# untitled.net
KiCad netlist of a schematic drawn in EAGLE
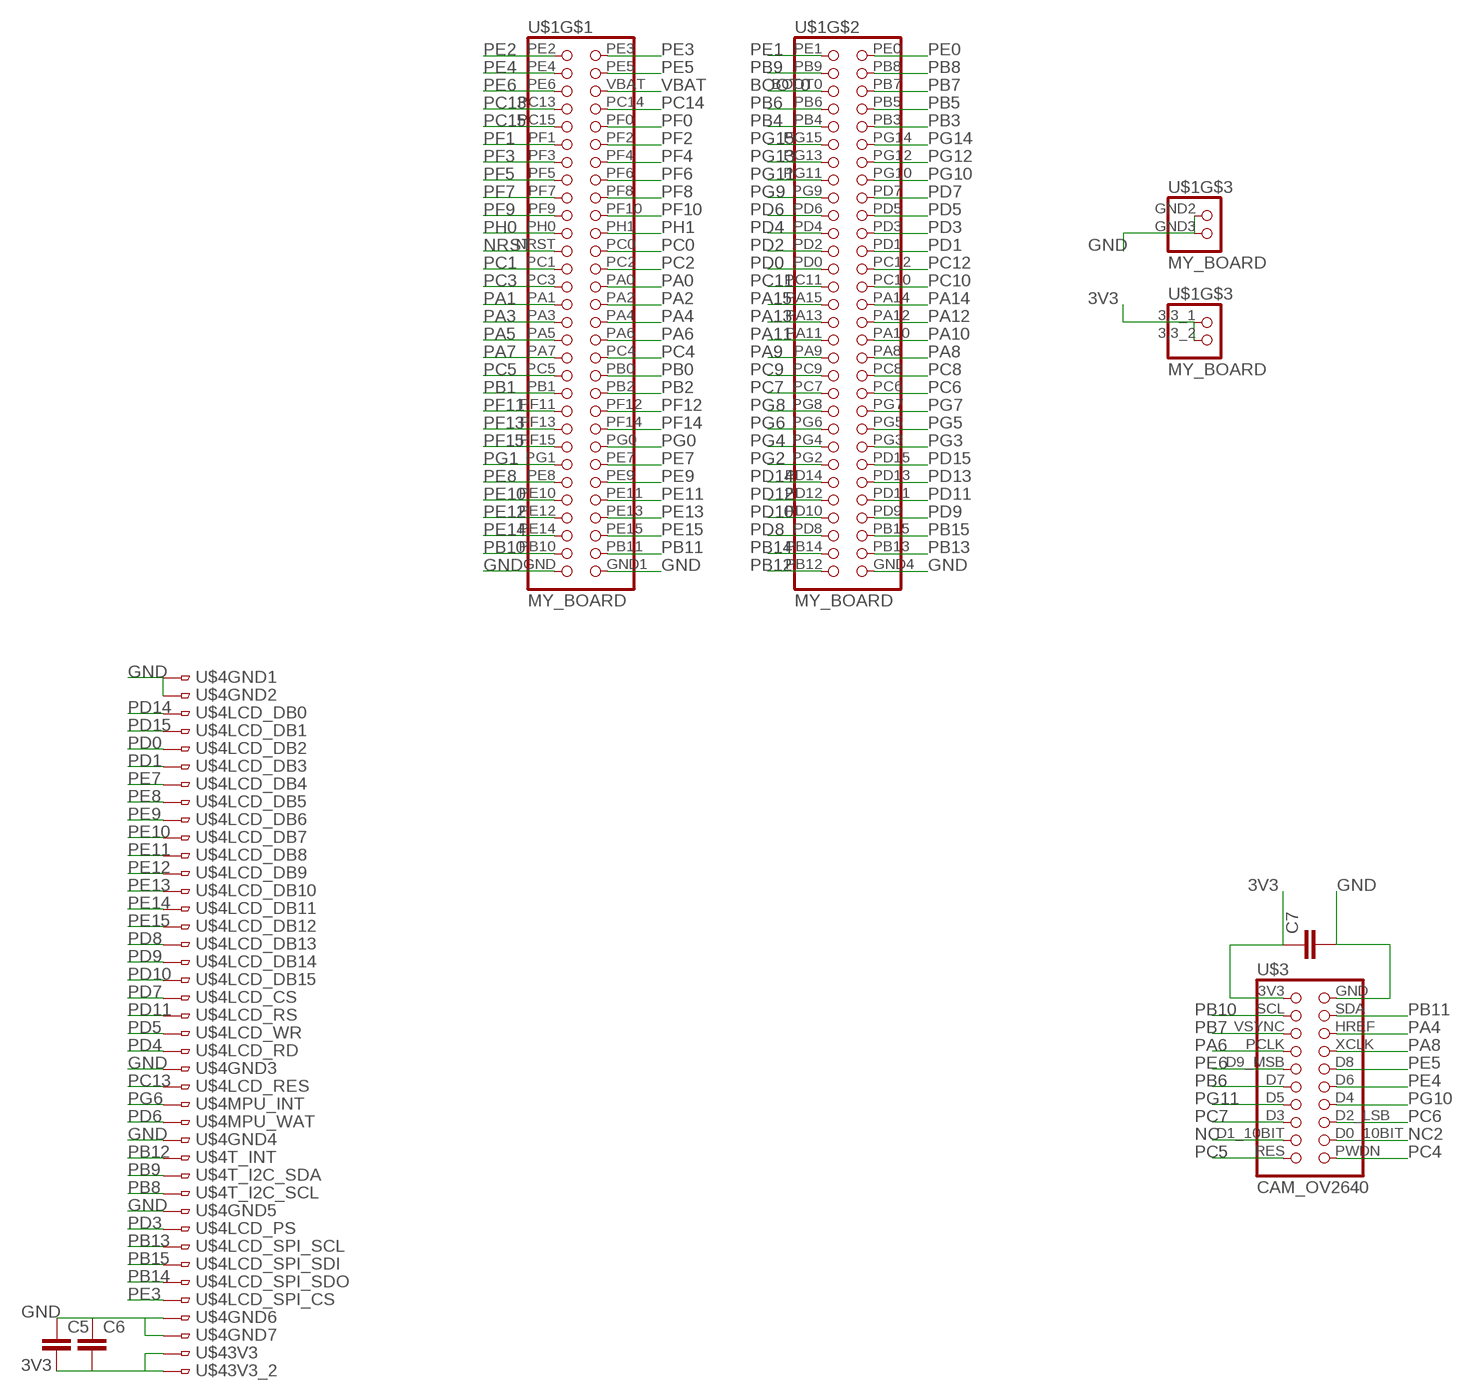
[diagram p0: schematic, sheet 1]

(export (version "E")
  (design (tool "Eeschema 10.0.6"))
  (components
    (comp (ref "C5")
      (value "C-EUC1206")
      (footprint "eagle-import:C1206")
      (libsource (lib "eagle-import") (part "C-EUC1206"))
    )
    (comp (ref "C6")
      (value "C-EUC1206")
      (footprint "eagle-import:C1206")
      (libsource (lib "eagle-import") (part "C-EUC1206"))
    )
    (comp (ref "C7")
      (value "C-EUC1206")
      (footprint "eagle-import:C1206")
      (libsource (lib "eagle-import") (part "C-EUC1206"))
    )
    (comp (ref "U$1")
      (value "MY_BOARD")
      (footprint "eagle-import:MY_BOARD")
      (libsource (lib "eagle-import") (part "MY_BOARD"))
    )
    (comp (ref "U$3")
      (value "CAM_OV2640")
      (footprint "eagle-import:CAM_OV2640")
      (libsource (lib "eagle-import") (part "CAM_OV2640"))
    )
    (comp (ref "U$4")
      (value "LCD800TFT")
      (footprint "eagle-import:FH12-40S-0.5SH")
      (libsource (lib "eagle-import") (part "LCD800TFT"))
    )
  )
  (nets
    (net (code "1") (name "/3V3") (class "Default")
      (node (ref "C5") (pin "2") (pinfunction "2_2") (pintype "passive"))
      (node (ref "C6") (pin "2") (pinfunction "2_2") (pintype "passive"))
      (node (ref "C7") (pin "1") (pinfunction "1_1") (pintype "passive"))
      (node (ref "U$1") (pin "3,3_1") (pinfunction "1_3,3_1") (pintype "passive"))
      (node (ref "U$1") (pin "3,3_2") (pinfunction "2_3,3_2") (pintype "passive"))
      (node (ref "U$3") (pin "3V3") (pinfunction "3V3_3V3") (pintype "passive"))
      (node (ref "U$4") (pin "39") (pinfunction "1_39") (pintype "passive"))
      (node (ref "U$4") (pin "40") (pinfunction "1_40") (pintype "passive"))
    )
    (net (code "2") (name "/BOOT0") (class "Default")
      (node (ref "U$1") (pin "BOOT0") (pinfunction "5_BOOT0") (pintype "passive"))
    )
    (net (code "3") (name "/GND") (class "Default")
      (node (ref "C5") (pin "1") (pinfunction "1_1") (pintype "passive"))
      (node (ref "C6") (pin "1") (pinfunction "1_1") (pintype "passive"))
      (node (ref "C7") (pin "2") (pinfunction "2_2") (pintype "passive"))
      (node (ref "U$1") (pin "GND") (pinfunction "59_GND") (pintype "passive"))
      (node (ref "U$1") (pin "GND1") (pinfunction "60_GND1") (pintype "passive"))
      (node (ref "U$1") (pin "GND2") (pinfunction "3_GND2") (pintype "passive"))
      (node (ref "U$1") (pin "GND3") (pinfunction "4_GND3") (pintype "passive"))
      (node (ref "U$1") (pin "GND4") (pinfunction "60_GND4") (pintype "passive"))
      (node (ref "U$3") (pin "GND") (pinfunction "GND_GND") (pintype "passive"))
      (node (ref "U$4") (pin "1") (pinfunction "1_1") (pintype "passive"))
      (node (ref "U$4") (pin "2") (pinfunction "1_2") (pintype "passive"))
      (node (ref "U$4") (pin "23") (pinfunction "1_23") (pintype "passive"))
      (node (ref "U$4") (pin "27") (pinfunction "1_27") (pintype "passive"))
      (node (ref "U$4") (pin "31") (pinfunction "1_31") (pintype "passive"))
      (node (ref "U$4") (pin "37") (pinfunction "1_37") (pintype "passive"))
      (node (ref "U$4") (pin "38") (pinfunction "1_38") (pintype "passive"))
    )
    (net (code "4") (name "/NC") (class "Default")
      (node (ref "U$3") (pin "D1_10BIT") (pinfunction "D1_10BIT_D1_10BIT") (pintype "passive"))
    )
    (net (code "5") (name "/NC2") (class "Default")
      (node (ref "U$3") (pin "D0_10BIT") (pinfunction "D0_10BIT_D0_10BIT") (pintype "passive"))
    )
    (net (code "6") (name "/NRST") (class "Default")
      (node (ref "U$1") (pin "NRST") (pinfunction "23_NRST") (pintype "passive"))
    )
    (net (code "7") (name "/PA0") (class "Default")
      (node (ref "U$1") (pin "PA0") (pinfunction "28_PA0") (pintype "passive"))
    )
    (net (code "8") (name "/PA1") (class "Default")
      (node (ref "U$1") (pin "PA1") (pinfunction "29_PA1") (pintype "passive"))
    )
    (net (code "9") (name "/PA2") (class "Default")
      (node (ref "U$1") (pin "PA2") (pinfunction "30_PA2") (pintype "passive"))
    )
    (net (code "10") (name "/PA3") (class "Default")
      (node (ref "U$1") (pin "PA3") (pinfunction "31_PA3") (pintype "passive"))
    )
    (net (code "11") (name "/PA4") (class "Default")
      (node (ref "U$1") (pin "PA4") (pinfunction "32_PA4") (pintype "passive"))
      (node (ref "U$3") (pin "HREF") (pinfunction "HREF_HREF") (pintype "passive"))
    )
    (net (code "12") (name "/PA5") (class "Default")
      (node (ref "U$1") (pin "PA5") (pinfunction "33_PA5") (pintype "passive"))
    )
    (net (code "13") (name "/PA6") (class "Default")
      (node (ref "U$1") (pin "PA6") (pinfunction "34_PA6") (pintype "passive"))
      (node (ref "U$3") (pin "PCLK") (pinfunction "PCLK_PCLK") (pintype "passive"))
    )
    (net (code "14") (name "/PA7") (class "Default")
      (node (ref "U$1") (pin "PA7") (pinfunction "35_PA7") (pintype "passive"))
    )
    (net (code "15") (name "/PA8") (class "Default")
      (node (ref "U$1") (pin "PA8") (pinfunction "36_PA8") (pintype "passive"))
      (node (ref "U$3") (pin "XCLK") (pinfunction "XCLK_XCLK") (pintype "passive"))
    )
    (net (code "16") (name "/PA9") (class "Default")
      (node (ref "U$1") (pin "PA9") (pinfunction "35_PA9") (pintype "passive"))
    )
    (net (code "17") (name "/PA10") (class "Default")
      (node (ref "U$1") (pin "PA10") (pinfunction "34_PA10") (pintype "passive"))
    )
    (net (code "18") (name "/PA11") (class "Default")
      (node (ref "U$1") (pin "PA11") (pinfunction "33_PA11") (pintype "passive"))
    )
    (net (code "19") (name "/PA12") (class "Default")
      (node (ref "U$1") (pin "PA12") (pinfunction "32_PA12") (pintype "passive"))
    )
    (net (code "20") (name "/PA13") (class "Default")
      (node (ref "U$1") (pin "PA13") (pinfunction "31_PA13") (pintype "passive"))
    )
    (net (code "21") (name "/PA14") (class "Default")
      (node (ref "U$1") (pin "PA14") (pinfunction "30_PA14") (pintype "passive"))
    )
    (net (code "22") (name "/PA15") (class "Default")
      (node (ref "U$1") (pin "PA15") (pinfunction "29_PA15") (pintype "passive"))
    )
    (net (code "23") (name "/PB0") (class "Default")
      (node (ref "U$1") (pin "PB0") (pinfunction "38_PB0") (pintype "passive"))
    )
    (net (code "24") (name "/PB1") (class "Default")
      (node (ref "U$1") (pin "PB1") (pinfunction "39_PB1") (pintype "passive"))
    )
    (net (code "25") (name "/PB2") (class "Default")
      (node (ref "U$1") (pin "PB2") (pinfunction "40_PB2") (pintype "passive"))
    )
    (net (code "26") (name "/PB3") (class "Default")
      (node (ref "U$1") (pin "PB3") (pinfunction "10_PB3") (pintype "passive"))
    )
    (net (code "27") (name "/PB4") (class "Default")
      (node (ref "U$1") (pin "PB4") (pinfunction "9_PB4") (pintype "passive"))
    )
    (net (code "28") (name "/PB5") (class "Default")
      (node (ref "U$1") (pin "PB5") (pinfunction "8_PB5") (pintype "passive"))
    )
    (net (code "29") (name "/PB6") (class "Default")
      (node (ref "U$1") (pin "PB6") (pinfunction "7_PB6") (pintype "passive"))
      (node (ref "U$3") (pin "D7") (pinfunction "D7_D7") (pintype "passive"))
    )
    (net (code "30") (name "/PB7") (class "Default")
      (node (ref "U$1") (pin "PB7") (pinfunction "6_PB7") (pintype "passive"))
      (node (ref "U$3") (pin "VSYNC") (pinfunction "VSYNC_VSYNC") (pintype "passive"))
    )
    (net (code "31") (name "/PB8") (class "Default")
      (node (ref "U$1") (pin "PB8") (pinfunction "4_PB8") (pintype "passive"))
      (node (ref "U$4") (pin "30") (pinfunction "1_30") (pintype "passive"))
    )
    (net (code "32") (name "/PB9") (class "Default")
      (node (ref "U$1") (pin "PB9") (pinfunction "3_PB9") (pintype "passive"))
      (node (ref "U$4") (pin "29") (pinfunction "1_29") (pintype "passive"))
    )
    (net (code "33") (name "/PB10") (class "Default")
      (node (ref "U$1") (pin "PB10") (pinfunction "57_PB10") (pintype "passive"))
      (node (ref "U$3") (pin "SCL") (pinfunction "SCL_SCL") (pintype "passive"))
    )
    (net (code "34") (name "/PB11") (class "Default")
      (node (ref "U$1") (pin "PB11") (pinfunction "58_PB11") (pintype "passive"))
      (node (ref "U$3") (pin "SDA") (pinfunction "SDA_SDA") (pintype "passive"))
    )
    (net (code "35") (name "/PB12") (class "Default")
      (node (ref "U$1") (pin "PB12") (pinfunction "59_PB12") (pintype "passive"))
      (node (ref "U$4") (pin "28") (pinfunction "1_28") (pintype "passive"))
    )
    (net (code "36") (name "/PB13") (class "Default")
      (node (ref "U$1") (pin "PB13") (pinfunction "58_PB13") (pintype "passive"))
      (node (ref "U$4") (pin "33") (pinfunction "1_33") (pintype "passive"))
    )
    (net (code "37") (name "/PB14") (class "Default")
      (node (ref "U$1") (pin "PB14") (pinfunction "57_PB14") (pintype "passive"))
      (node (ref "U$4") (pin "35") (pinfunction "1_35") (pintype "passive"))
    )
    (net (code "38") (name "/PB15") (class "Default")
      (node (ref "U$1") (pin "PB15") (pinfunction "56_PB15") (pintype "passive"))
      (node (ref "U$4") (pin "34") (pinfunction "1_34") (pintype "passive"))
    )
    (net (code "39") (name "/PC0") (class "Default")
      (node (ref "U$1") (pin "PC0") (pinfunction "24_PC0") (pintype "passive"))
    )
    (net (code "40") (name "/PC1") (class "Default")
      (node (ref "U$1") (pin "PC1") (pinfunction "25_PC1") (pintype "passive"))
    )
    (net (code "41") (name "/PC2") (class "Default")
      (node (ref "U$1") (pin "PC2") (pinfunction "26_PC2") (pintype "passive"))
    )
    (net (code "42") (name "/PC3") (class "Default")
      (node (ref "U$1") (pin "PC3") (pinfunction "27_PC3") (pintype "passive"))
    )
    (net (code "43") (name "/PC4") (class "Default")
      (node (ref "U$1") (pin "PC4") (pinfunction "36_PC4") (pintype "passive"))
      (node (ref "U$3") (pin "PWDN") (pinfunction "PWDN_PWDN") (pintype "passive"))
    )
    (net (code "44") (name "/PC5") (class "Default")
      (node (ref "U$1") (pin "PC5") (pinfunction "37_PC5") (pintype "passive"))
      (node (ref "U$3") (pin "RES") (pinfunction "RES_RES") (pintype "passive"))
    )
    (net (code "45") (name "/PC6") (class "Default")
      (node (ref "U$1") (pin "PC6") (pinfunction "40_PC6") (pintype "passive"))
      (node (ref "U$3") (pin "D2_LSB") (pinfunction "D2_LSB_D2_LSB") (pintype "passive"))
    )
    (net (code "46") (name "/PC7") (class "Default")
      (node (ref "U$1") (pin "PC7") (pinfunction "39_PC7") (pintype "passive"))
      (node (ref "U$3") (pin "D3") (pinfunction "D3_D3") (pintype "passive"))
    )
    (net (code "47") (name "/PC8") (class "Default")
      (node (ref "U$1") (pin "PC8") (pinfunction "38_PC8") (pintype "passive"))
    )
    (net (code "48") (name "/PC9") (class "Default")
      (node (ref "U$1") (pin "PC9") (pinfunction "37_PC9") (pintype "passive"))
    )
    (net (code "49") (name "/PC10") (class "Default")
      (node (ref "U$1") (pin "PC10") (pinfunction "28_PC10") (pintype "passive"))
    )
    (net (code "50") (name "/PC11") (class "Default")
      (node (ref "U$1") (pin "PC11") (pinfunction "27_PC11") (pintype "passive"))
    )
    (net (code "51") (name "/PC12") (class "Default")
      (node (ref "U$1") (pin "PC12") (pinfunction "26_PC12") (pintype "passive"))
    )
    (net (code "52") (name "/PC13") (class "Default")
      (node (ref "U$1") (pin "PC13") (pinfunction "7_PC13") (pintype "passive"))
      (node (ref "U$4") (pin "24") (pinfunction "1_24") (pintype "passive"))
    )
    (net (code "53") (name "/PC14") (class "Default")
      (node (ref "U$1") (pin "PC14") (pinfunction "8_PC14") (pintype "passive"))
    )
    (net (code "54") (name "/PC15") (class "Default")
      (node (ref "U$1") (pin "PC15") (pinfunction "9_PC15") (pintype "passive"))
    )
    (net (code "55") (name "/PD0") (class "Default")
      (node (ref "U$1") (pin "PD0") (pinfunction "25_PD0") (pintype "passive"))
      (node (ref "U$4") (pin "5") (pinfunction "1_5") (pintype "passive"))
    )
    (net (code "56") (name "/PD1") (class "Default")
      (node (ref "U$1") (pin "PD1") (pinfunction "24_PD1") (pintype "passive"))
      (node (ref "U$4") (pin "6") (pinfunction "1_6") (pintype "passive"))
    )
    (net (code "57") (name "/PD2") (class "Default")
      (node (ref "U$1") (pin "PD2") (pinfunction "23_PD2") (pintype "passive"))
    )
    (net (code "58") (name "/PD3") (class "Default")
      (node (ref "U$1") (pin "PD3") (pinfunction "22_PD3") (pintype "passive"))
      (node (ref "U$4") (pin "32") (pinfunction "1_32") (pintype "passive"))
    )
    (net (code "59") (name "/PD4") (class "Default")
      (node (ref "U$1") (pin "PD4") (pinfunction "21_PD4") (pintype "passive"))
      (node (ref "U$4") (pin "22") (pinfunction "1_22") (pintype "passive"))
    )
    (net (code "60") (name "/PD5") (class "Default")
      (node (ref "U$1") (pin "PD5") (pinfunction "20_PD5") (pintype "passive"))
      (node (ref "U$4") (pin "21") (pinfunction "1_21") (pintype "passive"))
    )
    (net (code "61") (name "/PD6") (class "Default")
      (node (ref "U$1") (pin "PD6") (pinfunction "19_PD6") (pintype "passive"))
      (node (ref "U$4") (pin "26") (pinfunction "1_26") (pintype "passive"))
    )
    (net (code "62") (name "/PD7") (class "Default")
      (node (ref "U$1") (pin "PD7") (pinfunction "18_PD7") (pintype "passive"))
      (node (ref "U$4") (pin "19") (pinfunction "1_19") (pintype "passive"))
    )
    (net (code "63") (name "/PD8") (class "Default")
      (node (ref "U$1") (pin "PD8") (pinfunction "55_PD8") (pintype "passive"))
      (node (ref "U$4") (pin "16") (pinfunction "1_16") (pintype "passive"))
    )
    (net (code "64") (name "/PD9") (class "Default")
      (node (ref "U$1") (pin "PD9") (pinfunction "54_PD9") (pintype "passive"))
      (node (ref "U$4") (pin "17") (pinfunction "1_17") (pintype "passive"))
    )
    (net (code "65") (name "/PD10") (class "Default")
      (node (ref "U$1") (pin "PD10") (pinfunction "53_PD10") (pintype "passive"))
      (node (ref "U$4") (pin "18") (pinfunction "1_18") (pintype "passive"))
    )
    (net (code "66") (name "/PD11") (class "Default")
      (node (ref "U$1") (pin "PD11") (pinfunction "52_PD11") (pintype "passive"))
      (node (ref "U$4") (pin "20") (pinfunction "1_20") (pintype "passive"))
    )
    (net (code "67") (name "/PD12") (class "Default")
      (node (ref "U$1") (pin "PD12") (pinfunction "51_PD12") (pintype "passive"))
    )
    (net (code "68") (name "/PD13") (class "Default")
      (node (ref "U$1") (pin "PD13") (pinfunction "50_PD13") (pintype "passive"))
    )
    (net (code "69") (name "/PD14") (class "Default")
      (node (ref "U$1") (pin "PD14") (pinfunction "49_PD14") (pintype "passive"))
      (node (ref "U$4") (pin "3") (pinfunction "1_3") (pintype "passive"))
    )
    (net (code "70") (name "/PD15") (class "Default")
      (node (ref "U$1") (pin "PD15") (pinfunction "48_PD15") (pintype "passive"))
      (node (ref "U$4") (pin "4") (pinfunction "1_4") (pintype "passive"))
    )
    (net (code "71") (name "/PE0") (class "Default")
      (node (ref "U$1") (pin "PE0") (pinfunction "2_PE0") (pintype "passive"))
    )
    (net (code "72") (name "/PE1") (class "Default")
      (node (ref "U$1") (pin "PE1") (pinfunction "1_PE1") (pintype "passive"))
    )
    (net (code "73") (name "/PE2") (class "Default")
      (node (ref "U$1") (pin "PE2") (pinfunction "1_PE2") (pintype "passive"))
    )
    (net (code "74") (name "/PE3") (class "Default")
      (node (ref "U$1") (pin "PE3") (pinfunction "2_PE3") (pintype "passive"))
      (node (ref "U$4") (pin "36") (pinfunction "1_36") (pintype "passive"))
    )
    (net (code "75") (name "/PE4") (class "Default")
      (node (ref "U$1") (pin "PE4") (pinfunction "3_PE4") (pintype "passive"))
      (node (ref "U$3") (pin "D6") (pinfunction "D6_D6") (pintype "passive"))
    )
    (net (code "76") (name "/PE5") (class "Default")
      (node (ref "U$1") (pin "PE5") (pinfunction "4_PE5") (pintype "passive"))
      (node (ref "U$3") (pin "D8") (pinfunction "D8_D8") (pintype "passive"))
    )
    (net (code "77") (name "/PE6") (class "Default")
      (node (ref "U$1") (pin "PE6") (pinfunction "5_PE6") (pintype "passive"))
      (node (ref "U$3") (pin "D9_MSB") (pinfunction "D9_MSB_D9_MSB") (pintype "passive"))
    )
    (net (code "78") (name "/PE7") (class "Default")
      (node (ref "U$1") (pin "PE7") (pinfunction "48_PE7") (pintype "passive"))
      (node (ref "U$4") (pin "7") (pinfunction "1_7") (pintype "passive"))
    )
    (net (code "79") (name "/PE8") (class "Default")
      (node (ref "U$1") (pin "PE8") (pinfunction "49_PE8") (pintype "passive"))
      (node (ref "U$4") (pin "8") (pinfunction "1_8") (pintype "passive"))
    )
    (net (code "80") (name "/PE9") (class "Default")
      (node (ref "U$1") (pin "PE9") (pinfunction "50_PE9") (pintype "passive"))
      (node (ref "U$4") (pin "9") (pinfunction "1_9") (pintype "passive"))
    )
    (net (code "81") (name "/PE10") (class "Default")
      (node (ref "U$1") (pin "PE10") (pinfunction "51_PE10") (pintype "passive"))
      (node (ref "U$4") (pin "10") (pinfunction "1_10") (pintype "passive"))
    )
    (net (code "82") (name "/PE11") (class "Default")
      (node (ref "U$1") (pin "PE11") (pinfunction "52_PE11") (pintype "passive"))
      (node (ref "U$4") (pin "11") (pinfunction "1_11") (pintype "passive"))
    )
    (net (code "83") (name "/PE12") (class "Default")
      (node (ref "U$1") (pin "PE12") (pinfunction "53_PE12") (pintype "passive"))
      (node (ref "U$4") (pin "12") (pinfunction "1_12") (pintype "passive"))
    )
    (net (code "84") (name "/PE13") (class "Default")
      (node (ref "U$1") (pin "PE13") (pinfunction "54_PE13") (pintype "passive"))
      (node (ref "U$4") (pin "13") (pinfunction "1_13") (pintype "passive"))
    )
    (net (code "85") (name "/PE14") (class "Default")
      (node (ref "U$1") (pin "PE14") (pinfunction "55_PE14") (pintype "passive"))
      (node (ref "U$4") (pin "14") (pinfunction "1_14") (pintype "passive"))
    )
    (net (code "86") (name "/PE15") (class "Default")
      (node (ref "U$1") (pin "PE15") (pinfunction "56_PE15") (pintype "passive"))
      (node (ref "U$4") (pin "15") (pinfunction "1_15") (pintype "passive"))
    )
    (net (code "87") (name "/PF0") (class "Default")
      (node (ref "U$1") (pin "PF0") (pinfunction "10_PF0") (pintype "passive"))
    )
    (net (code "88") (name "/PF1") (class "Default")
      (node (ref "U$1") (pin "PF1") (pinfunction "11_PF1") (pintype "passive"))
    )
    (net (code "89") (name "/PF2") (class "Default")
      (node (ref "U$1") (pin "PF2") (pinfunction "12_PF2") (pintype "passive"))
    )
    (net (code "90") (name "/PF3") (class "Default")
      (node (ref "U$1") (pin "PF3") (pinfunction "13_PF3") (pintype "passive"))
    )
    (net (code "91") (name "/PF4") (class "Default")
      (node (ref "U$1") (pin "PF4") (pinfunction "14_PF4") (pintype "passive"))
    )
    (net (code "92") (name "/PF5") (class "Default")
      (node (ref "U$1") (pin "PF5") (pinfunction "15_PF5") (pintype "passive"))
    )
    (net (code "93") (name "/PF6") (class "Default")
      (node (ref "U$1") (pin "PF6") (pinfunction "16_PF6") (pintype "passive"))
    )
    (net (code "94") (name "/PF7") (class "Default")
      (node (ref "U$1") (pin "PF7") (pinfunction "17_PF7") (pintype "passive"))
    )
    (net (code "95") (name "/PF8") (class "Default")
      (node (ref "U$1") (pin "PF8") (pinfunction "18_PF8") (pintype "passive"))
    )
    (net (code "96") (name "/PF9") (class "Default")
      (node (ref "U$1") (pin "PF9") (pinfunction "19_PF9") (pintype "passive"))
    )
    (net (code "97") (name "/PF10") (class "Default")
      (node (ref "U$1") (pin "PF10") (pinfunction "20_PF10") (pintype "passive"))
    )
    (net (code "98") (name "/PF11") (class "Default")
      (node (ref "U$1") (pin "PF11") (pinfunction "41_PF11") (pintype "passive"))
    )
    (net (code "99") (name "/PF12") (class "Default")
      (node (ref "U$1") (pin "PF12") (pinfunction "42_PF12") (pintype "passive"))
    )
    (net (code "100") (name "/PF13") (class "Default")
      (node (ref "U$1") (pin "PF13") (pinfunction "43_PF13") (pintype "passive"))
    )
    (net (code "101") (name "/PF14") (class "Default")
      (node (ref "U$1") (pin "PF14") (pinfunction "44_PF14") (pintype "passive"))
    )
    (net (code "102") (name "/PF15") (class "Default")
      (node (ref "U$1") (pin "PF15") (pinfunction "45_PF15") (pintype "passive"))
    )
    (net (code "103") (name "/PG0") (class "Default")
      (node (ref "U$1") (pin "PG0") (pinfunction "46_PG0") (pintype "passive"))
    )
    (net (code "104") (name "/PG1") (class "Default")
      (node (ref "U$1") (pin "PG1") (pinfunction "47_PG1") (pintype "passive"))
    )
    (net (code "105") (name "/PG2") (class "Default")
      (node (ref "U$1") (pin "PG2") (pinfunction "47_PG2") (pintype "passive"))
    )
    (net (code "106") (name "/PG3") (class "Default")
      (node (ref "U$1") (pin "PG3") (pinfunction "46_PG3") (pintype "passive"))
    )
    (net (code "107") (name "/PG4") (class "Default")
      (node (ref "U$1") (pin "PG4") (pinfunction "45_PG4") (pintype "passive"))
    )
    (net (code "108") (name "/PG5") (class "Default")
      (node (ref "U$1") (pin "PG5") (pinfunction "44_PG5") (pintype "passive"))
    )
    (net (code "109") (name "/PG6") (class "Default")
      (node (ref "U$1") (pin "PG6") (pinfunction "43_PG6") (pintype "passive"))
      (node (ref "U$4") (pin "25") (pinfunction "1_25") (pintype "passive"))
    )
    (net (code "110") (name "/PG7") (class "Default")
      (node (ref "U$1") (pin "PG7") (pinfunction "42_PG7") (pintype "passive"))
    )
    (net (code "111") (name "/PG8") (class "Default")
      (node (ref "U$1") (pin "PG8") (pinfunction "41_PG8") (pintype "passive"))
    )
    (net (code "112") (name "/PG9") (class "Default")
      (node (ref "U$1") (pin "PG9") (pinfunction "17_PG9") (pintype "passive"))
    )
    (net (code "113") (name "/PG10") (class "Default")
      (node (ref "U$1") (pin "PG10") (pinfunction "16_PG10") (pintype "passive"))
      (node (ref "U$3") (pin "D4") (pinfunction "D4_D4") (pintype "passive"))
    )
    (net (code "114") (name "/PG11") (class "Default")
      (node (ref "U$1") (pin "PG11") (pinfunction "15_PG11") (pintype "passive"))
      (node (ref "U$3") (pin "D5") (pinfunction "D5_D5") (pintype "passive"))
    )
    (net (code "115") (name "/PG12") (class "Default")
      (node (ref "U$1") (pin "PG12") (pinfunction "14_PG12") (pintype "passive"))
    )
    (net (code "116") (name "/PG13") (class "Default")
      (node (ref "U$1") (pin "PG13") (pinfunction "13_PG13") (pintype "passive"))
    )
    (net (code "117") (name "/PG14") (class "Default")
      (node (ref "U$1") (pin "PG14") (pinfunction "12_PG14") (pintype "passive"))
    )
    (net (code "118") (name "/PG15") (class "Default")
      (node (ref "U$1") (pin "PG15") (pinfunction "11_PG15") (pintype "passive"))
    )
    (net (code "119") (name "/PH0") (class "Default")
      (node (ref "U$1") (pin "PH0") (pinfunction "21_PH0") (pintype "passive"))
    )
    (net (code "120") (name "/PH1") (class "Default")
      (node (ref "U$1") (pin "PH1") (pinfunction "22_PH1") (pintype "passive"))
    )
    (net (code "121") (name "/VBAT") (class "Default")
      (node (ref "U$1") (pin "VBAT") (pinfunction "6_VBAT") (pintype "passive"))
    )
  )
)
